# MCU.net
KiCad netlist of a schematic drawn in Altium Designer
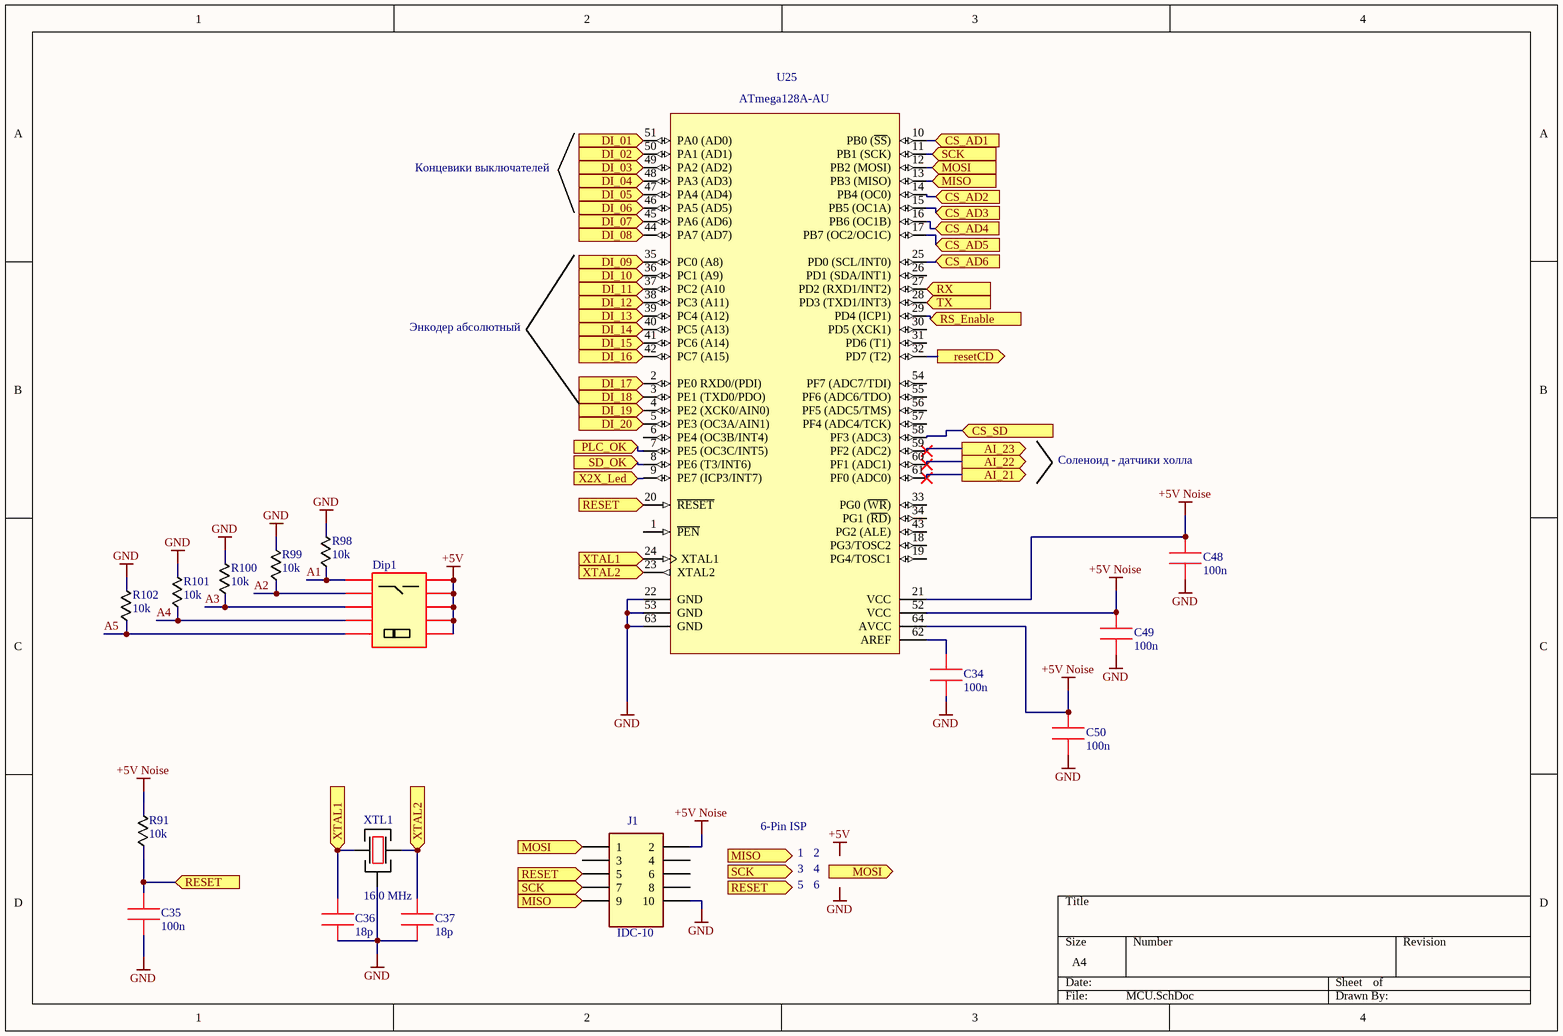
[diagram p0: MCU.SchDoc]

(export (version "E")
  (design (tool "Eeschema 10.0.6"))
  (components
    (comp (ref "C34")
      (value "100n")
      (footprint "0603")
      (description "CC0603KRX7R9BB104")
      (libsource (lib "kontr") (part "0603 CAP"))
    )
    (comp (ref "C35")
      (value "100n")
      (footprint "0603")
      (description "CC0603KRX7R9BB104")
      (libsource (lib "kontr") (part "0603 CAP"))
    )
    (comp (ref "C36")
      (value "18p")
      (footprint "0603")
      (description "CC0603JRNPO9BN180")
      (libsource (lib "kontr") (part "0603 CAP"))
    )
    (comp (ref "C37")
      (value "18p")
      (footprint "0603")
      (description "CC0603JRNPO9BN180")
      (libsource (lib "kontr") (part "0603 CAP"))
    )
    (comp (ref "C48")
      (value "100n")
      (footprint "0603")
      (description "CC0603KRX7R9BB104")
      (libsource (lib "kontr") (part "0603 CAP"))
    )
    (comp (ref "C49")
      (value "100n")
      (footprint "0603")
      (description "CC0603KRX7R9BB104")
      (libsource (lib "kontr") (part "0603 CAP"))
    )
    (comp (ref "C50")
      (value "100n")
      (footprint "0603")
      (description "CC0603KRX7R9BB104")
      (libsource (lib "kontr") (part "0603 CAP"))
    )
    (comp (ref "Dip1")
      (value "DS1040-05RT")
      (footprint "DipSwitch 5")
      (description "DPL-05-V")
      (libsource (lib "kontr") (part "DipSwitch5"))
    )
    (comp (ref "J1")
      (value "IDC-10")
      (footprint "IDC-10MS")
      (description "DS1013-10SSIB1-B-0")
      (libsource (lib "kontr") (part "IDC-10MS"))
    )
    (comp (ref "R91")
      (value "10k")
      (footprint "0603")
      (description "RT0603FRE0710KL")
      (libsource (lib "kontr") (part "0603 RES"))
    )
    (comp (ref "R98")
      (value "10k")
      (footprint "0603")
      (description "RT0603FRE0710KL")
      (libsource (lib "kontr") (part "0603 RES"))
    )
    (comp (ref "R99")
      (value "10k")
      (footprint "0603")
      (description "RT0603FRE0710KL")
      (libsource (lib "kontr") (part "0603 RES"))
    )
    (comp (ref "R100")
      (value "10k")
      (footprint "0603")
      (description "RT0603FRE0710KL")
      (libsource (lib "kontr") (part "0603 RES"))
    )
    (comp (ref "R101")
      (value "10k")
      (footprint "0603")
      (description "RT0603FRE0710KL")
      (libsource (lib "kontr") (part "0603 RES"))
    )
    (comp (ref "R102")
      (value "10k")
      (footprint "0603")
      (description "RT0603FRE0710KL")
      (libsource (lib "kontr") (part "0603 RES"))
    )
    (comp (ref "U25")
      (value "ATmega128A-AU")
      (footprint "64A_N")
      (libsource (lib "Atmel Microcontroller megaAVR") (part "ATmega128A-AU"))
    )
    (comp (ref "XTL1")
      (value "16.0 MHz")
      (footprint "ABM10")
      (description "12.88605")
      (libsource (lib "kontr") (part "KX-7"))
    )
  )
  (nets
    (net (code "1") (name "+5V") (class "Default")
      (node (ref "Dip1") (pin "1") (pinfunction "1_1") (pintype "passive"))
      (node (ref "Dip1") (pin "2") (pinfunction "3_2") (pintype "passive"))
      (node (ref "Dip1") (pin "3") (pinfunction "5_3") (pintype "passive"))
      (node (ref "Dip1") (pin "4") (pinfunction "7_4") (pintype "passive"))
      (node (ref "Dip1") (pin "5") (pinfunction "9_5") (pintype "passive"))
    )
    (net (code "2") (name "+5V Noise") (class "Default")
      (node (ref "C48") (pin "2") (pinfunction "2_2") (pintype "passive"))
      (node (ref "C49") (pin "2") (pinfunction "2_2") (pintype "passive"))
      (node (ref "C50") (pin "2") (pinfunction "2_2") (pintype "passive"))
      (node (ref "J1") (pin "2") (pinfunction "2_2") (pintype "passive"))
      (node (ref "R91") (pin "2") (pintype "passive"))
      (node (ref "U25") (pin "21") (pinfunction "VCC_21") (pintype "power_in"))
      (node (ref "U25") (pin "52") (pinfunction "VCC_52") (pintype "power_in"))
      (node (ref "U25") (pin "64") (pinfunction "AVCC_64") (pintype "power_in"))
    )
    (net (code "3") (name "/A1") (class "Default")
      (node (ref "Dip1") (pin "12") (pinfunction "10_12") (pintype "passive"))
      (node (ref "R98") (pin "1") (pintype "passive"))
    )
    (net (code "4") (name "/A2") (class "Default")
      (node (ref "Dip1") (pin "13") (pinfunction "8_13") (pintype "passive"))
      (node (ref "R99") (pin "1") (pintype "passive"))
    )
    (net (code "5") (name "/A3") (class "Default")
      (node (ref "Dip1") (pin "14") (pinfunction "6_14") (pintype "passive"))
      (node (ref "R100") (pin "1") (pintype "passive"))
    )
    (net (code "6") (name "/A4") (class "Default")
      (node (ref "Dip1") (pin "15") (pinfunction "4_15") (pintype "passive"))
      (node (ref "R101") (pin "1") (pintype "passive"))
    )
    (net (code "7") (name "/A5") (class "Default")
      (node (ref "Dip1") (pin "16") (pinfunction "2_16") (pintype "passive"))
      (node (ref "R102") (pin "1") (pintype "passive"))
    )
    (net (code "8") (name "/AI_21") (class "Default")
      (node (ref "U25") (pin "61") (pinfunction "PF0_(ADC0)_61") (pintype "bidirectional+no_connect"))
    )
    (net (code "9") (name "/AI_22") (class "Default")
      (node (ref "U25") (pin "60") (pinfunction "PF1_(ADC1)_60") (pintype "bidirectional+no_connect"))
    )
    (net (code "10") (name "/AI_23") (class "Default")
      (node (ref "U25") (pin "59") (pinfunction "PF2_(ADC2)_59") (pintype "bidirectional+no_connect"))
    )
    (net (code "11") (name "/CS_AD1") (class "Default")
      (node (ref "U25") (pin "10") (pinfunction "PB0_(~{SS})_10") (pintype "bidirectional"))
    )
    (net (code "12") (name "/CS_AD2") (class "Default")
      (node (ref "U25") (pin "14") (pinfunction "PB4_(OC0)_14") (pintype "bidirectional"))
    )
    (net (code "13") (name "/CS_AD3") (class "Default")
      (node (ref "U25") (pin "15") (pinfunction "PB5_(OC1A)_15") (pintype "bidirectional"))
    )
    (net (code "14") (name "/CS_AD4") (class "Default")
      (node (ref "U25") (pin "16") (pinfunction "PB6_(OC1B)_16") (pintype "bidirectional"))
    )
    (net (code "15") (name "/CS_AD5") (class "Default")
      (node (ref "U25") (pin "17") (pinfunction "PB7_(OC2/OC1C)_17") (pintype "bidirectional"))
    )
    (net (code "16") (name "/CS_AD6") (class "Default")
      (node (ref "U25") (pin "25") (pinfunction "PD0_(SCL/INT0)_25") (pintype "bidirectional"))
    )
    (net (code "17") (name "/CS_SD") (class "Default")
      (node (ref "U25") (pin "58") (pinfunction "PF3_(ADC3)_58") (pintype "bidirectional"))
    )
    (net (code "18") (name "/DI_01") (class "Default")
      (node (ref "U25") (pin "51") (pinfunction "PA0_(AD0)_51") (pintype "bidirectional"))
    )
    (net (code "19") (name "/DI_02") (class "Default")
      (node (ref "U25") (pin "50") (pinfunction "PA1_(AD1)_50") (pintype "bidirectional"))
    )
    (net (code "20") (name "/DI_03") (class "Default")
      (node (ref "U25") (pin "49") (pinfunction "PA2_(AD2)_49") (pintype "bidirectional"))
    )
    (net (code "21") (name "/DI_04") (class "Default")
      (node (ref "U25") (pin "48") (pinfunction "PA3_(AD3)_48") (pintype "bidirectional"))
    )
    (net (code "22") (name "/DI_05") (class "Default")
      (node (ref "U25") (pin "47") (pinfunction "PA4_(AD4)_47") (pintype "bidirectional"))
    )
    (net (code "23") (name "/DI_06") (class "Default")
      (node (ref "U25") (pin "46") (pinfunction "PA5_(AD5)_46") (pintype "bidirectional"))
    )
    (net (code "24") (name "/DI_07") (class "Default")
      (node (ref "U25") (pin "45") (pinfunction "PA6_(AD6)_45") (pintype "bidirectional"))
    )
    (net (code "25") (name "/DI_08") (class "Default")
      (node (ref "U25") (pin "44") (pinfunction "PA7_(AD7)_44") (pintype "bidirectional"))
    )
    (net (code "26") (name "/DI_09") (class "Default")
      (node (ref "U25") (pin "35") (pinfunction "PC0_(A8)_35") (pintype "bidirectional"))
    )
    (net (code "27") (name "/DI_10") (class "Default")
      (node (ref "U25") (pin "36") (pinfunction "PC1_(A9)_36") (pintype "bidirectional"))
    )
    (net (code "28") (name "/DI_11") (class "Default")
      (node (ref "U25") (pin "37") (pinfunction "PC2_(A10_37") (pintype "bidirectional"))
    )
    (net (code "29") (name "/DI_12") (class "Default")
      (node (ref "U25") (pin "38") (pinfunction "PC3_(A11)_38") (pintype "bidirectional"))
    )
    (net (code "30") (name "/DI_13") (class "Default")
      (node (ref "U25") (pin "39") (pinfunction "PC4_(A12)_39") (pintype "bidirectional"))
    )
    (net (code "31") (name "/DI_14") (class "Default")
      (node (ref "U25") (pin "40") (pinfunction "PC5_(A13)_40") (pintype "bidirectional"))
    )
    (net (code "32") (name "/DI_15") (class "Default")
      (node (ref "U25") (pin "41") (pinfunction "PC6_(A14)_41") (pintype "bidirectional"))
    )
    (net (code "33") (name "/DI_16") (class "Default")
      (node (ref "U25") (pin "42") (pinfunction "PC7_(A15)_42") (pintype "bidirectional"))
    )
    (net (code "34") (name "/DI_17") (class "Default")
      (node (ref "U25") (pin "2") (pinfunction "PE0_RXD0/(PDI)_2") (pintype "bidirectional"))
    )
    (net (code "35") (name "/DI_18") (class "Default")
      (node (ref "U25") (pin "3") (pinfunction "PE1_(TXD0/PDO)_3") (pintype "bidirectional"))
    )
    (net (code "36") (name "/DI_19") (class "Default")
      (node (ref "U25") (pin "4") (pinfunction "PE2_(XCK0/AIN0)_4") (pintype "bidirectional"))
    )
    (net (code "37") (name "/DI_20") (class "Default")
      (node (ref "U25") (pin "5") (pinfunction "PE3_(OC3A/AIN1)_5") (pintype "bidirectional"))
    )
    (net (code "38") (name "/MISO") (class "Default")
      (node (ref "J1") (pin "9") (pinfunction "9_9") (pintype "passive"))
      (node (ref "U25") (pin "13") (pinfunction "PB3_(MISO)_13") (pintype "bidirectional"))
    )
    (net (code "39") (name "/MOSI") (class "Default")
      (node (ref "J1") (pin "1") (pinfunction "1_1") (pintype "passive"))
      (node (ref "U25") (pin "12") (pinfunction "PB2_(MOSI)_12") (pintype "bidirectional"))
    )
    (net (code "40") (name "/PLC_OK") (class "Default")
      (node (ref "U25") (pin "7") (pinfunction "PE5_(OC3C/INT5)_7") (pintype "bidirectional"))
    )
    (net (code "41") (name "/RESET") (class "Default")
      (node (ref "C35") (pin "2") (pinfunction "2_2") (pintype "passive"))
      (node (ref "J1") (pin "5") (pinfunction "5_5") (pintype "passive"))
      (node (ref "R91") (pin "1") (pintype "passive"))
      (node (ref "U25") (pin "20") (pinfunction "~{RESET}_20") (pintype "input"))
    )
    (net (code "42") (name "/RS_Enable") (class "Default")
      (node (ref "U25") (pin "29") (pinfunction "PD4_(ICP1)_29") (pintype "bidirectional"))
    )
    (net (code "43") (name "/RX") (class "Default")
      (node (ref "U25") (pin "27") (pinfunction "PD2_(RXD1/INT2)_27") (pintype "bidirectional"))
    )
    (net (code "44") (name "/SCK") (class "Default")
      (node (ref "J1") (pin "7") (pinfunction "7_7") (pintype "passive"))
      (node (ref "U25") (pin "11") (pinfunction "PB1_(SCK)_11") (pintype "bidirectional"))
    )
    (net (code "45") (name "/SD_OK") (class "Default")
      (node (ref "U25") (pin "8") (pinfunction "PE6_(T3/INT6)_8") (pintype "bidirectional"))
    )
    (net (code "46") (name "/TX") (class "Default")
      (node (ref "U25") (pin "28") (pinfunction "PD3_(TXD1/INT3)_28") (pintype "bidirectional"))
    )
    (net (code "47") (name "/X2X_Led") (class "Default")
      (node (ref "U25") (pin "9") (pinfunction "PE7_(ICP3/INT7)_9") (pintype "bidirectional"))
    )
    (net (code "48") (name "/XTAL1") (class "Default")
      (node (ref "C36") (pin "2") (pinfunction "2_2") (pintype "passive"))
      (node (ref "U25") (pin "24") (pinfunction "XTAL1_24") (pintype "input"))
      (node (ref "XTL1") (pin "1") (pinfunction "5_1") (pintype "passive"))
    )
    (net (code "49") (name "/XTAL2") (class "Default")
      (node (ref "C37") (pin "2") (pinfunction "2_2") (pintype "passive"))
      (node (ref "U25") (pin "23") (pinfunction "XTAL2_23") (pintype "output"))
      (node (ref "XTL1") (pin "3") (pinfunction "5_3") (pintype "passive"))
    )
    (net (code "50") (name "/resetCD") (class "Default")
      (node (ref "U25") (pin "32") (pinfunction "PD7_(T2)_32") (pintype "bidirectional"))
    )
    (net (code "51") (name "GND") (class "Default")
      (node (ref "C34") (pin "1") (pinfunction "1_1") (pintype "passive"))
      (node (ref "C35") (pin "1") (pinfunction "1_1") (pintype "passive"))
      (node (ref "C36") (pin "1") (pinfunction "1_1") (pintype "passive"))
      (node (ref "C37") (pin "1") (pinfunction "1_1") (pintype "passive"))
      (node (ref "C48") (pin "1") (pinfunction "1_1") (pintype "passive"))
      (node (ref "C49") (pin "1") (pinfunction "1_1") (pintype "passive"))
      (node (ref "C50") (pin "1") (pinfunction "1_1") (pintype "passive"))
      (node (ref "J1") (pin "10") (pinfunction "10_10") (pintype "passive"))
      (node (ref "R100") (pin "2") (pintype "passive"))
      (node (ref "R101") (pin "2") (pintype "passive"))
      (node (ref "R102") (pin "2") (pintype "passive"))
      (node (ref "R98") (pin "2") (pintype "passive"))
      (node (ref "R99") (pin "2") (pintype "passive"))
      (node (ref "U25") (pin "22") (pinfunction "GND_22") (pintype "power_in"))
      (node (ref "U25") (pin "53") (pinfunction "GND_53") (pintype "power_in"))
      (node (ref "U25") (pin "63") (pinfunction "GND_63") (pintype "power_in"))
      (node (ref "XTL1") (pin "2") (pinfunction "2_2") (pintype "passive"))
    )
    (net (code "52") (name "Net-(U25-AREF)") (class "Default")
      (node (ref "C34") (pin "2") (pinfunction "2_2") (pintype "passive"))
      (node (ref "U25") (pin "62") (pinfunction "AREF_62") (pintype "power_in"))
    )
    (net (code "53") (name "unconnected-(J1-Pad3)") (class "Default")
      (node (ref "J1") (pin "3") (pinfunction "3_3") (pintype "passive"))
    )
    (net (code "54") (name "unconnected-(J1-Pad4)") (class "Default")
      (node (ref "J1") (pin "4") (pinfunction "4_4") (pintype "passive"))
    )
    (net (code "55") (name "unconnected-(J1-Pad6)") (class "Default")
      (node (ref "J1") (pin "6") (pinfunction "6_6") (pintype "passive"))
    )
    (net (code "56") (name "unconnected-(J1-Pad8)") (class "Default")
      (node (ref "J1") (pin "8") (pinfunction "8_8") (pintype "passive"))
    )
    (net (code "57") (name "unconnected-(U25-PD1_(SDA{slash}INT1)-Pad26)") (class "Default")
      (node (ref "U25") (pin "26") (pinfunction "PD1_(SDA/INT1)_26") (pintype "bidirectional"))
    )
    (net (code "58") (name "unconnected-(U25-PD5_(XCK1)-Pad30)") (class "Default")
      (node (ref "U25") (pin "30") (pinfunction "PD5_(XCK1)_30") (pintype "bidirectional"))
    )
    (net (code "59") (name "unconnected-(U25-PD6_(T1)-Pad31)") (class "Default")
      (node (ref "U25") (pin "31") (pinfunction "PD6_(T1)_31") (pintype "bidirectional"))
    )
    (net (code "60") (name "unconnected-(U25-PE4_(OC3B{slash}INT4)-Pad6)") (class "Default")
      (node (ref "U25") (pin "6") (pinfunction "PE4_(OC3B/INT4)_6") (pintype "bidirectional"))
    )
    (net (code "61") (name "unconnected-(U25-PF4_(ADC4{slash}TCK)-Pad57)") (class "Default")
      (node (ref "U25") (pin "57") (pinfunction "PF4_(ADC4/TCK)_57") (pintype "bidirectional"))
    )
    (net (code "62") (name "unconnected-(U25-PF5_(ADC5{slash}TMS)-Pad56)") (class "Default")
      (node (ref "U25") (pin "56") (pinfunction "PF5_(ADC5/TMS)_56") (pintype "bidirectional"))
    )
    (net (code "63") (name "unconnected-(U25-PF6_(ADC6{slash}TDO)-Pad55)") (class "Default")
      (node (ref "U25") (pin "55") (pinfunction "PF6_(ADC6/TDO)_55") (pintype "bidirectional"))
    )
    (net (code "64") (name "unconnected-(U25-PF7_(ADC7{slash}TDI)-Pad54)") (class "Default")
      (node (ref "U25") (pin "54") (pinfunction "PF7_(ADC7/TDI)_54") (pintype "bidirectional"))
    )
    (net (code "65") (name "unconnected-(U25-PG0_(~{WR})-Pad33)") (class "Default")
      (node (ref "U25") (pin "33") (pinfunction "PG0_(~{WR})_33") (pintype "bidirectional"))
    )
    (net (code "66") (name "unconnected-(U25-PG1_(~{RD})-Pad34)") (class "Default")
      (node (ref "U25") (pin "34") (pinfunction "PG1_(~{RD})_34") (pintype "bidirectional"))
    )
    (net (code "67") (name "unconnected-(U25-PG2_(ALE)-Pad43)") (class "Default")
      (node (ref "U25") (pin "43") (pinfunction "PG2_(ALE)_43") (pintype "bidirectional"))
    )
    (net (code "68") (name "unconnected-(U25-PG3{slash}TOSC2-Pad18)") (class "Default")
      (node (ref "U25") (pin "18") (pinfunction "PG3/TOSC2_18") (pintype "bidirectional"))
    )
    (net (code "69") (name "unconnected-(U25-PG4{slash}TOSC1-Pad19)") (class "Default")
      (node (ref "U25") (pin "19") (pinfunction "PG4/TOSC1_19") (pintype "bidirectional"))
    )
    (net (code "70") (name "unconnected-(U25-~{PEN}-Pad1)") (class "Default")
      (node (ref "U25") (pin "1") (pinfunction "~{PEN}_1") (pintype "input"))
    )
  )
)
